# Sch_pwr_brd_MCU.net
KiCad netlist of a schematic drawn in Altium Designer
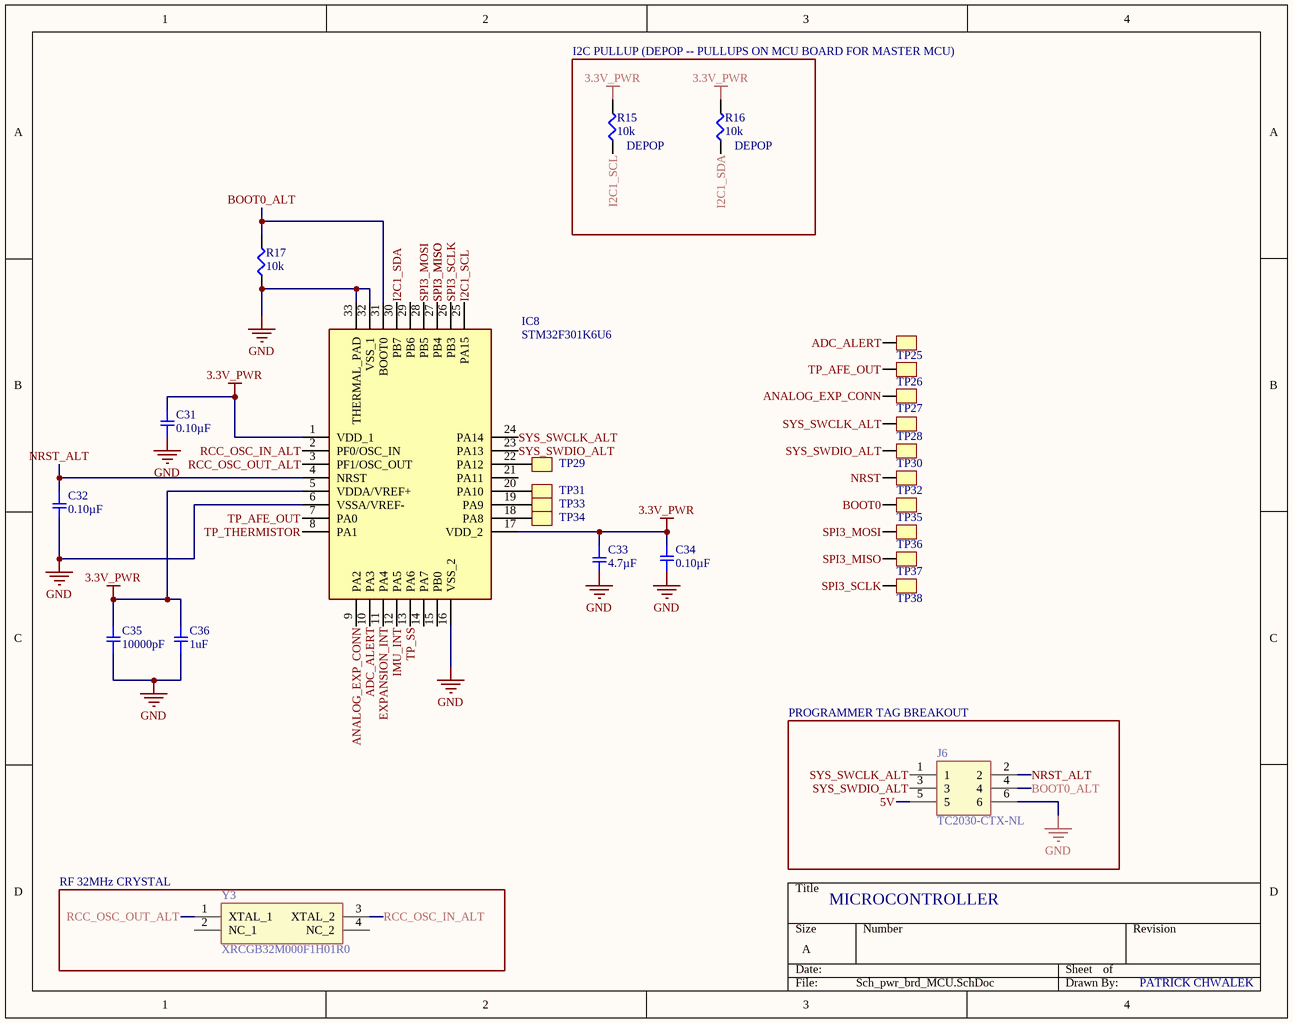
[diagram p0: Sch_pwr_brd_MCU.SchDoc]

(export (version "E")
  (design (tool "Eeschema 10.0.6"))
  (components
    (comp (ref "C31")
      (value "0.10µF")
      (footprint "SMD-0402C")
      (description "CAP CER 0.1UF 16V X7R 0402")
      (fields
        (field (name "DIGI-KEY PART NUMBER") "490-4759-1-ND")
        (field (name "PART NUMBER") "GCM155R71C104KA55D")
      )
      (libsource (lib "capacitor_murata_0402") (part "GCM155R71C104KA55D"))
    )
    (comp (ref "C32")
      (value "0.10µF")
      (footprint "SMD-0402C")
      (description "CAP CER 0.1UF 16V X7R 0402")
      (fields
        (field (name "DIGI-KEY PART NUMBER") "490-4759-1-ND")
        (field (name "PART NUMBER") "GCM155R71C104KA55D")
      )
      (libsource (lib "capacitor_murata_0402") (part "GCM155R71C104KA55D"))
    )
    (comp (ref "C33")
      (value "4.7µF")
      (footprint "SMD-0402C")
      (description "CAP CER 4.7UF 4V X5R 0402")
      (fields
        (field (name "DIGI-KEY PART NUMBER") "490-13231-1-ND")
        (field (name "PART NUMBER") "GRM153R60G475ME15D")
      )
      (libsource (lib "capacitor_murata_0402") (part "GRM153R60G475ME15D"))
    )
    (comp (ref "C34")
      (value "0.10µF")
      (footprint "SMD-0402C")
      (description "CAP CER 0.1UF 16V X7R 0402")
      (fields
        (field (name "DIGI-KEY PART NUMBER") "490-4759-1-ND")
        (field (name "PART NUMBER") "GCM155R71C104KA55D")
      )
      (libsource (lib "capacitor_murata_0402") (part "GCM155R71C104KA55D"))
    )
    (comp (ref "C35")
      (value "10000pF")
      (footprint "SMD-0402C")
      (description "CAP CER 10000PF 50V X7R 0402")
      (fields
        (field (name "DIGI-KEY PART NUMBER") "490-4762-1-ND")
        (field (name "PART NUMBER") "GCM155R71H103KA55D")
      )
      (libsource (lib "capacitor_murata_0402") (part "GCM155R71H103KA55D"))
    )
    (comp (ref "C36")
      (value "1uF")
      (footprint "SMD-0402C")
      (description "CAP CER 1UF 0402")
      (fields
        (field (name "DIGI-KEY PART NUMBER") "490-4762-1-ND")
        (field (name "PART NUMBER") "JMK105BJ105KP-F")
      )
      (libsource (lib "capacitor_murata_0402") (part "GCM155R71H103KA55D"))
    )
    (comp (ref "IC8")
      (value "STM32F301K6U6")
      (footprint "SamacSys:QFN50P500X500X60-33N-D")
      (description "Integrated Circuit")
      (fields (field (name "MOUSER PART NUMBER") "511-STM32F301K6U6"))
      (libsource (lib "*") (part "STM32F301K6U6"))
    )
    (comp (ref "J6")
      (value "TC2030-CTX-NL")
      (footprint "SamacSys:TC2030MCPNL10")
      (description "Connector")
      (libsource (lib "SamacSys") (part "TC2030-CTX-NL"))
    )
    (comp (ref "R15")
      (value "10k")
      (footprint "SMD-0402-RES")
      (description "RES SMD 10K OHM 5% 1/10W 0402")
      (fields (field (name "PART NUMBER") "ERJ-2GEJ103X") (field (name "DIGI-KEY PART NUMBER") "P10KJCT-ND"))
      (libsource (lib "Panasonic_ERJ_0402") (part "ERJ-2GEJ103X"))
    )
    (comp (ref "R16")
      (value "10k")
      (footprint "SMD-0402-RES")
      (description "RES SMD 10K OHM 5% 1/10W 0402")
      (fields (field (name "PART NUMBER") "ERJ-2GEJ103X") (field (name "DIGI-KEY PART NUMBER") "P10KJCT-ND"))
      (libsource (lib "Panasonic_ERJ_0402") (part "ERJ-2GEJ103X"))
    )
    (comp (ref "R17")
      (value "10k")
      (footprint "SMD-0402-RES")
      (description "RES SMD 10K OHM 5% 1/10W 0402")
      (fields (field (name "PART NUMBER") "ERJ-2GEJ103X") (field (name "DIGI-KEY PART NUMBER") "P10KJCT-ND"))
      (libsource (lib "Panasonic_ERJ_0402") (part "ERJ-2GEJ103X"))
    )
    (comp (ref "TP25")
      (value "TestPoint")
      (footprint "TestPoint_0.4mm")
      (libsource (lib "schematic_components") (part "TestPoint"))
    )
    (comp (ref "TP26")
      (value "TestPoint")
      (footprint "TestPoint_0.4mm")
      (libsource (lib "schematic_components") (part "TestPoint"))
    )
    (comp (ref "TP27")
      (value "TestPoint")
      (footprint "TestPoint_0.4mm")
      (libsource (lib "schematic_components") (part "TestPoint"))
    )
    (comp (ref "TP28")
      (value "TestPoint")
      (footprint "TestPoint_0.4mm")
      (libsource (lib "schematic_components") (part "TestPoint"))
    )
    (comp (ref "TP29")
      (value "TestPoint")
      (footprint "TESTPOINT_1MM_OVAL")
      (libsource (lib "schematic_components") (part "TestPoint"))
    )
    (comp (ref "TP30")
      (value "TestPoint")
      (footprint "TestPoint_0.4mm")
      (libsource (lib "schematic_components") (part "TestPoint"))
    )
    (comp (ref "TP31")
      (value "TestPoint")
      (footprint "TESTPOINT_1MM_OVAL")
      (libsource (lib "schematic_components") (part "TestPoint"))
    )
    (comp (ref "TP32")
      (value "TestPoint")
      (footprint "TestPoint_0.4mm")
      (libsource (lib "schematic_components") (part "TestPoint"))
    )
    (comp (ref "TP33")
      (value "TestPoint")
      (footprint "TESTPOINT_1MM_OVAL")
      (libsource (lib "schematic_components") (part "TestPoint"))
    )
    (comp (ref "TP34")
      (value "TestPoint")
      (footprint "TESTPOINT_1MM_OVAL")
      (libsource (lib "schematic_components") (part "TestPoint"))
    )
    (comp (ref "TP35")
      (value "TestPoint")
      (footprint "TestPoint_0.4mm")
      (libsource (lib "schematic_components") (part "TestPoint"))
    )
    (comp (ref "TP36")
      (value "TestPoint")
      (footprint "TestPoint_0.4mm")
      (libsource (lib "schematic_components") (part "TestPoint"))
    )
    (comp (ref "TP37")
      (value "TestPoint")
      (footprint "TestPoint_0.4mm")
      (libsource (lib "schematic_components") (part "TestPoint"))
    )
    (comp (ref "TP38")
      (value "TestPoint")
      (footprint "TestPoint_0.4mm")
      (libsource (lib "schematic_components") (part "TestPoint"))
    )
    (comp (ref "Y3")
      (value "XRCGB32M000F1H01R0")
      (footprint "SamacSys:XRCGB32M000F1H01R0")
      (description "Crystal or Oscillator")
      (fields (field (name "MOUSER PART NUMBER") "81-XRCGB32M000F1H01R"))
      (libsource (lib "SamacSys") (part "XRCGB32M000F1H01R0"))
    )
  )
  (nets
    (net (code "1") (name "/5V") (class "Default")
      (node (ref "J6") (pin "5") (pinfunction "5_5") (pintype "passive"))
    )
    (net (code "2") (name "/ADC_ALERT") (class "Default")
      (node (ref "IC8") (pin "10") (pinfunction "PA3_10") (pintype "passive"))
      (node (ref "TP25") (pin "1") (pinfunction "1_1") (pintype "passive"))
    )
    (net (code "3") (name "/ANALOG_EXP_CONN") (class "Default")
      (node (ref "IC8") (pin "9") (pinfunction "PA2_9") (pintype "passive"))
      (node (ref "TP27") (pin "1") (pinfunction "1_1") (pintype "passive"))
    )
    (net (code "4") (name "/BOOT0") (class "Default")
      (node (ref "TP35") (pin "1") (pinfunction "1_1") (pintype "passive"))
    )
    (net (code "5") (name "/BOOT0_ALT") (class "Default")
      (node (ref "IC8") (pin "31") (pinfunction "BOOT0_31") (pintype "passive"))
      (node (ref "J6") (pin "4") (pinfunction "4_4") (pintype "passive"))
      (node (ref "R17") (pin "2") (pinfunction "2_2") (pintype "passive"))
    )
    (net (code "6") (name "/EXPANSION_INT") (class "Default")
      (node (ref "IC8") (pin "11") (pinfunction "PA4_11") (pintype "passive"))
    )
    (net (code "7") (name "/I2C1_SCL") (class "Default")
      (node (ref "IC8") (pin "25") (pinfunction "PA15_25") (pintype "passive"))
      (node (ref "R15") (pin "1") (pinfunction "1_1") (pintype "passive"))
    )
    (net (code "8") (name "/I2C1_SDA") (class "Default")
      (node (ref "IC8") (pin "30") (pinfunction "PB7_30") (pintype "passive"))
      (node (ref "R16") (pin "1") (pinfunction "1_1") (pintype "passive"))
    )
    (net (code "9") (name "/IMU_INT") (class "Default")
      (node (ref "IC8") (pin "12") (pinfunction "PA5_12") (pintype "passive"))
    )
    (net (code "10") (name "/NRST") (class "Default")
      (node (ref "TP32") (pin "1") (pinfunction "1_1") (pintype "passive"))
    )
    (net (code "11") (name "/NRST_ALT") (class "Default")
      (node (ref "C32") (pin "1") (pinfunction "1_1") (pintype "passive"))
      (node (ref "IC8") (pin "4") (pinfunction "NRST_4") (pintype "passive"))
      (node (ref "J6") (pin "2") (pinfunction "2_2") (pintype "passive"))
    )
    (net (code "12") (name "/RCC_OSC_IN_ALT") (class "Default")
      (node (ref "IC8") (pin "2") (pinfunction "PF0/OSC_IN_2") (pintype "passive"))
      (node (ref "Y3") (pin "3") (pinfunction "XTAL_2_3") (pintype "passive"))
    )
    (net (code "13") (name "/RCC_OSC_OUT_ALT") (class "Default")
      (node (ref "IC8") (pin "3") (pinfunction "PF1/OSC_OUT_3") (pintype "passive"))
      (node (ref "Y3") (pin "1") (pinfunction "XTAL_1_1") (pintype "passive"))
    )
    (net (code "14") (name "/SPI3_MISO") (class "Default")
      (node (ref "IC8") (pin "27") (pinfunction "PB4_27") (pintype "passive"))
      (node (ref "TP37") (pin "1") (pinfunction "1_1") (pintype "passive"))
    )
    (net (code "15") (name "/SPI3_MOSI") (class "Default")
      (node (ref "IC8") (pin "28") (pinfunction "PB5_28") (pintype "passive"))
      (node (ref "TP36") (pin "1") (pinfunction "1_1") (pintype "passive"))
    )
    (net (code "16") (name "/SPI3_SCLK") (class "Default")
      (node (ref "IC8") (pin "26") (pinfunction "PB3_26") (pintype "passive"))
      (node (ref "TP38") (pin "1") (pinfunction "1_1") (pintype "passive"))
    )
    (net (code "17") (name "/SYS_SWCLK_ALT") (class "Default")
      (node (ref "IC8") (pin "24") (pinfunction "PA14_24") (pintype "passive"))
      (node (ref "J6") (pin "1") (pinfunction "1_1") (pintype "passive"))
      (node (ref "TP28") (pin "1") (pinfunction "1_1") (pintype "passive"))
    )
    (net (code "18") (name "/SYS_SWDIO_ALT") (class "Default")
      (node (ref "IC8") (pin "23") (pinfunction "PA13_23") (pintype "passive"))
      (node (ref "J6") (pin "3") (pinfunction "3_3") (pintype "passive"))
      (node (ref "TP30") (pin "1") (pinfunction "1_1") (pintype "passive"))
    )
    (net (code "19") (name "/TP_AFE_OUT") (class "Default")
      (node (ref "IC8") (pin "7") (pinfunction "PA0_7") (pintype "passive"))
      (node (ref "TP26") (pin "1") (pinfunction "1_1") (pintype "passive"))
    )
    (net (code "20") (name "/TP_SS") (class "Default")
      (node (ref "IC8") (pin "13") (pinfunction "PA6_13") (pintype "passive"))
    )
    (net (code "21") (name "/TP_THERMISTOR") (class "Default")
      (node (ref "IC8") (pin "8") (pinfunction "PA1_8") (pintype "passive"))
    )
    (net (code "22") (name "3.3V_PWR") (class "Default")
      (node (ref "C31") (pin "2") (pinfunction "2_2") (pintype "passive"))
      (node (ref "C33") (pin "1") (pinfunction "1_1") (pintype "passive"))
      (node (ref "C34") (pin "2") (pinfunction "2_2") (pintype "passive"))
      (node (ref "C35") (pin "2") (pinfunction "2_2") (pintype "passive"))
      (node (ref "C36") (pin "2") (pinfunction "2_2") (pintype "passive"))
      (node (ref "IC8") (pin "1") (pinfunction "VDD_1_1") (pintype "passive"))
      (node (ref "IC8") (pin "17") (pinfunction "VDD_2_17") (pintype "passive"))
      (node (ref "IC8") (pin "5") (pinfunction "VDDA/VREF+_5") (pintype "passive"))
      (node (ref "R15") (pin "2") (pinfunction "2_2") (pintype "passive"))
      (node (ref "R16") (pin "2") (pinfunction "2_2") (pintype "passive"))
    )
    (net (code "23") (name "GND") (class "Default")
      (node (ref "C31") (pin "1") (pinfunction "1_1") (pintype "passive"))
      (node (ref "C32") (pin "2") (pinfunction "2_2") (pintype "passive"))
      (node (ref "C33") (pin "2") (pinfunction "2_2") (pintype "passive"))
      (node (ref "C34") (pin "1") (pinfunction "1_1") (pintype "passive"))
      (node (ref "C35") (pin "1") (pinfunction "1_1") (pintype "passive"))
      (node (ref "C36") (pin "1") (pinfunction "1_1") (pintype "passive"))
      (node (ref "IC8") (pin "16") (pinfunction "VSS_2_16") (pintype "passive"))
      (node (ref "IC8") (pin "32") (pinfunction "VSS_1_32") (pintype "passive"))
      (node (ref "IC8") (pin "33") (pinfunction "THERMAL_PAD_33") (pintype "passive"))
      (node (ref "IC8") (pin "6") (pinfunction "VSSA/VREF-_6") (pintype "passive"))
      (node (ref "J6") (pin "6") (pinfunction "6_6") (pintype "passive"))
      (node (ref "R17") (pin "1") (pinfunction "1_1") (pintype "passive"))
    )
    (net (code "24") (name "Net-(IC8-PA8)") (class "Default")
      (node (ref "IC8") (pin "18") (pinfunction "PA8_18") (pintype "passive"))
      (node (ref "TP34") (pin "1") (pinfunction "1_1") (pintype "passive"))
    )
    (net (code "25") (name "Net-(IC8-PA9)") (class "Default")
      (node (ref "IC8") (pin "19") (pinfunction "PA9_19") (pintype "passive"))
      (node (ref "TP33") (pin "1") (pinfunction "1_1") (pintype "passive"))
    )
    (net (code "26") (name "Net-(IC8-PA10)") (class "Default")
      (node (ref "IC8") (pin "20") (pinfunction "PA10_20") (pintype "passive"))
      (node (ref "TP31") (pin "1") (pinfunction "1_1") (pintype "passive"))
    )
    (net (code "27") (name "Net-(IC8-PA12)") (class "Default")
      (node (ref "IC8") (pin "22") (pinfunction "PA12_22") (pintype "passive"))
      (node (ref "TP29") (pin "1") (pinfunction "1_1") (pintype "passive"))
    )
    (net (code "28") (name "unconnected-(IC8-PA7-Pad14)") (class "Default")
      (node (ref "IC8") (pin "14") (pinfunction "PA7_14") (pintype "passive"))
    )
    (net (code "29") (name "unconnected-(IC8-PA11-Pad21)") (class "Default")
      (node (ref "IC8") (pin "21") (pinfunction "PA11_21") (pintype "passive"))
    )
    (net (code "30") (name "unconnected-(IC8-PB0-Pad15)") (class "Default")
      (node (ref "IC8") (pin "15") (pinfunction "PB0_15") (pintype "passive"))
    )
    (net (code "31") (name "unconnected-(IC8-PB6-Pad29)") (class "Default")
      (node (ref "IC8") (pin "29") (pinfunction "PB6_29") (pintype "passive"))
    )
    (net (code "32") (name "unconnected-(Y3-NC_1-Pad2)") (class "Default")
      (node (ref "Y3") (pin "2") (pinfunction "NC_1_2") (pintype "passive"))
    )
    (net (code "33") (name "unconnected-(Y3-NC_2-Pad4)") (class "Default")
      (node (ref "Y3") (pin "4") (pinfunction "NC_2_4") (pintype "passive"))
    )
  )
)
